# uicc.net
KiCad netlist of a schematic drawn in Altium Designer
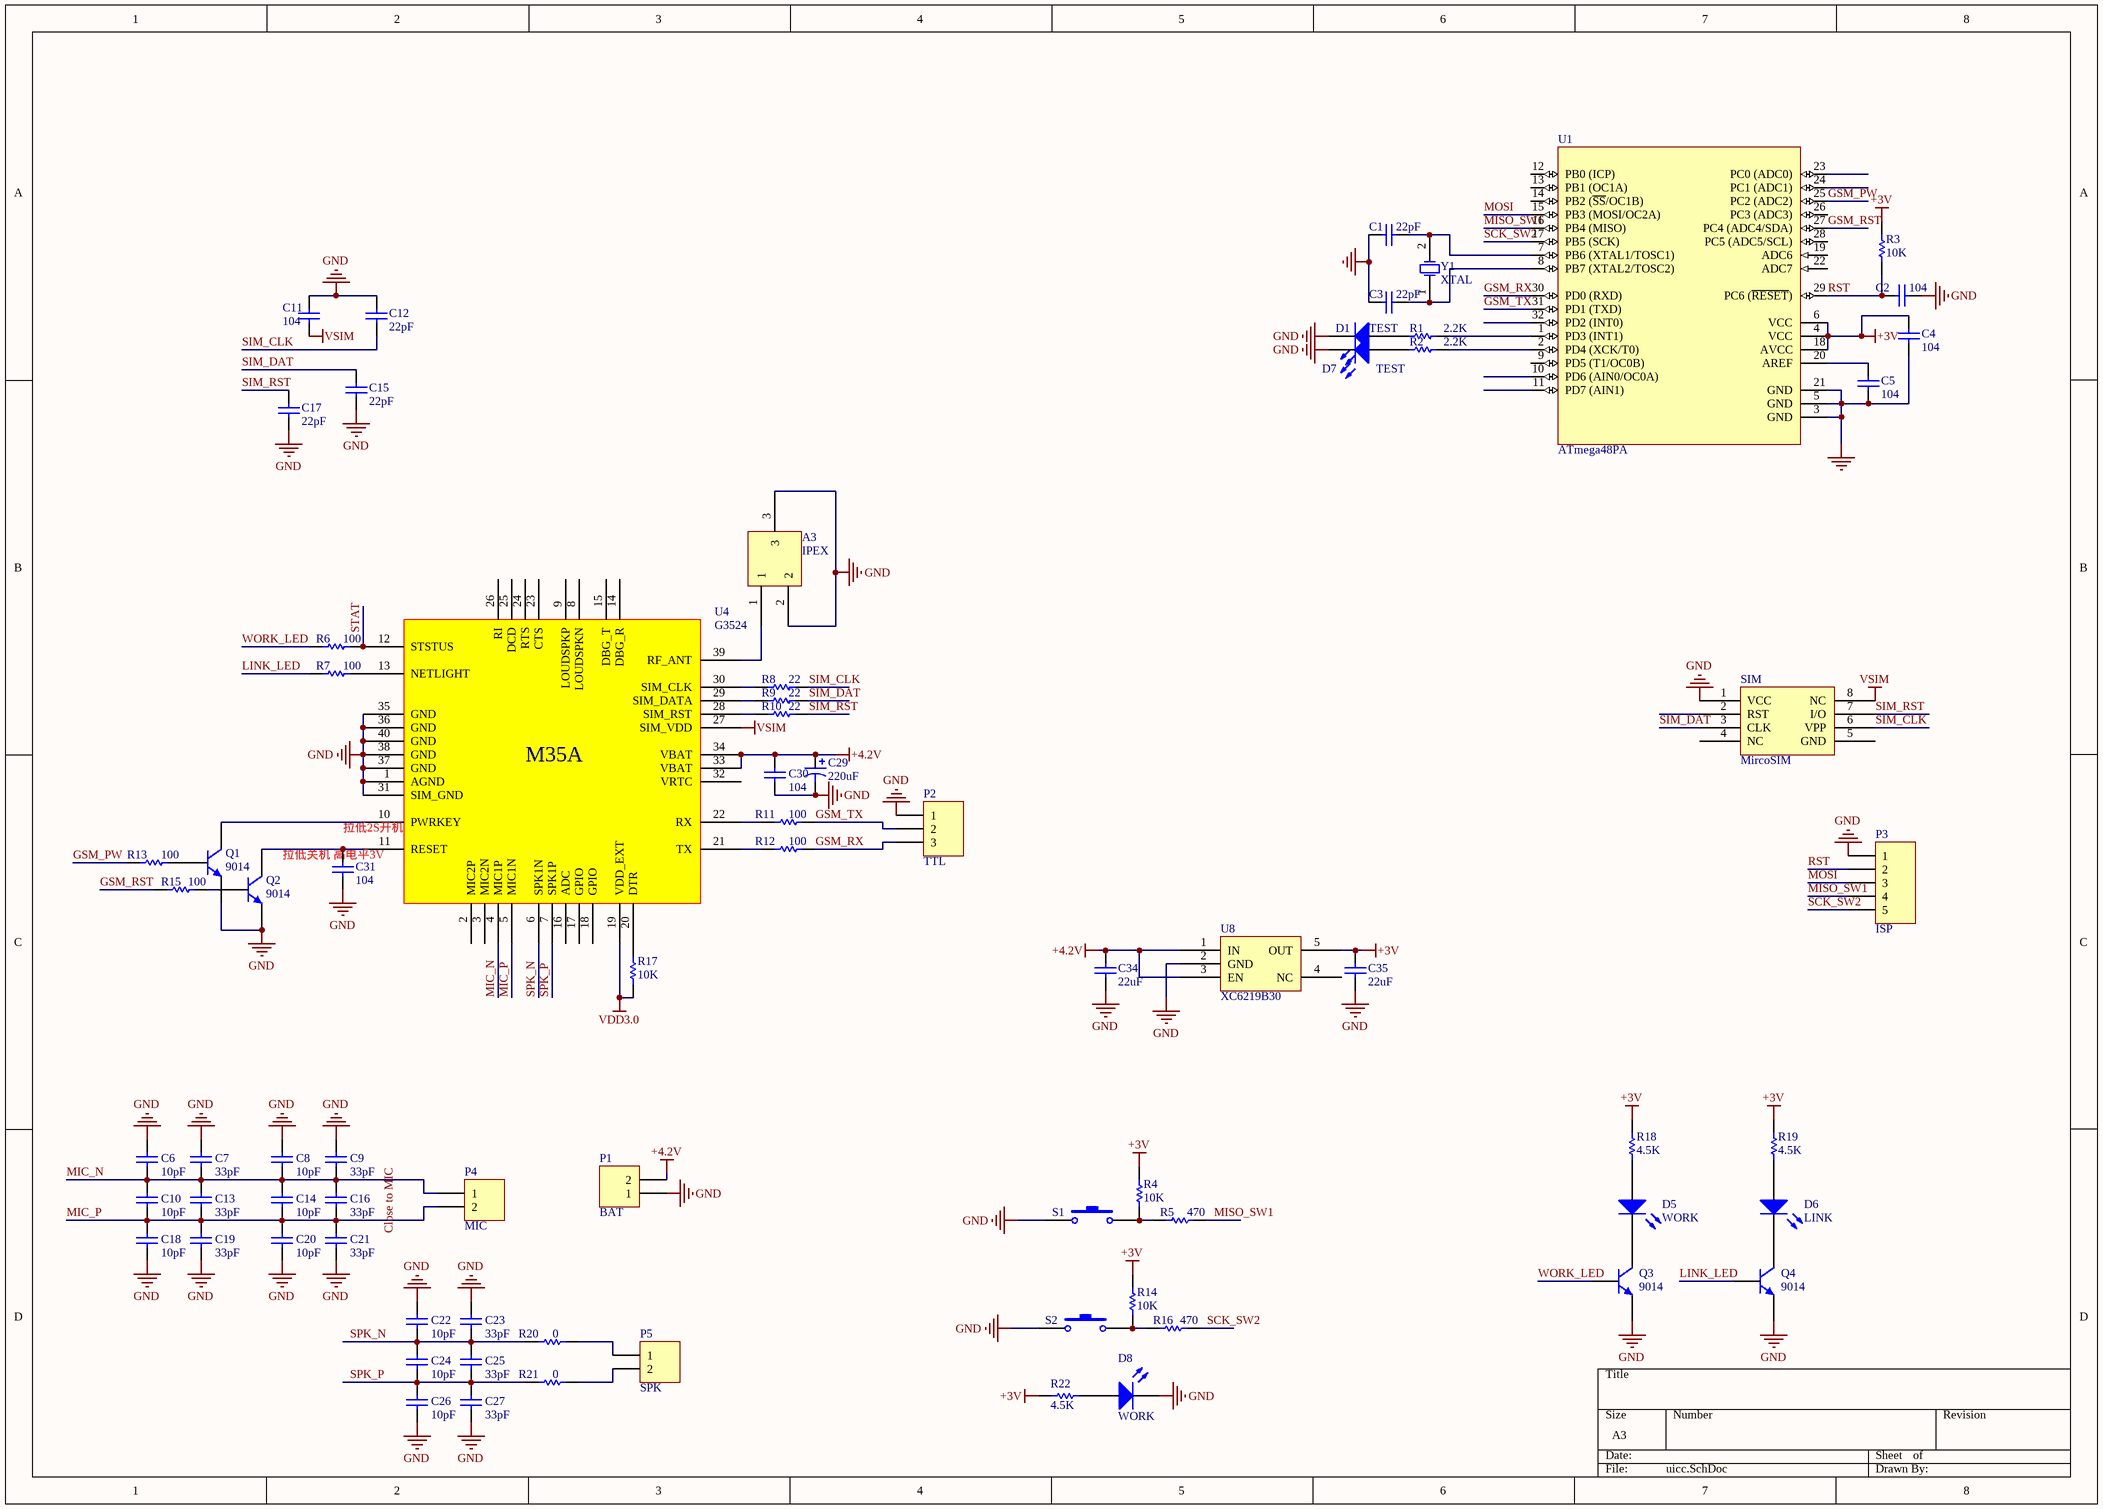
[diagram p0: uicc.SchDoc]

(export (version "E")
  (design (tool "Eeschema 10.0.6"))
  (components
    (comp (ref "A3") (value "IPEX") (footprint "IPEX") (libsource (lib "TANK") (part "IPEX")))
    (comp (ref "C1")
      (value "22pF")
      (footprint "0603C")
      (description "Capacitor")
      (fields (field (name "Comment") "Cap") (field (name "PUBLISHER") "Altium Limited"))
      (libsource (lib "*") (part "Cap"))
    )
    (comp (ref "C2")
      (value "104")
      (footprint "0603C")
      (description "Capacitor")
      (fields (field (name "Comment") "Cap") (field (name "PUBLISHER") "Altium Limited"))
      (libsource (lib "Miscellaneous Devices") (part "Cap"))
    )
    (comp (ref "C3")
      (value "22pF")
      (footprint "0603C")
      (description "Capacitor")
      (fields (field (name "Comment") "Cap") (field (name "PUBLISHER") "Altium Limited"))
      (libsource (lib "*") (part "Cap"))
    )
    (comp (ref "C4")
      (value "104")
      (footprint "0603C")
      (description "Capacitor")
      (fields (field (name "Comment") "Cap") (field (name "PUBLISHER") "Altium Limited"))
      (libsource (lib "Miscellaneous Devices") (part "Cap"))
    )
    (comp (ref "C5")
      (value "104")
      (footprint "0603C")
      (description "Capacitor")
      (fields (field (name "Comment") "Cap") (field (name "PUBLISHER") "Altium Limited"))
      (libsource (lib "*") (part "Cap"))
    )
    (comp (ref "C6")
      (value "10pF")
      (footprint "0603R")
      (description "Capacitor")
      (fields (field (name "Comment") "Cap") (field (name "PUBLISHER") "Altium Limited"))
      (libsource (lib "Miscellaneous Devices") (part "Cap"))
    )
    (comp (ref "C7")
      (value "33pF")
      (footprint "0603R")
      (description "Capacitor")
      (fields (field (name "Comment") "Cap") (field (name "PUBLISHER") "Altium Limited"))
      (libsource (lib "Miscellaneous Devices") (part "Cap"))
    )
    (comp (ref "C8")
      (value "10pF")
      (footprint "0603R")
      (description "Capacitor")
      (fields (field (name "Comment") "Cap") (field (name "PUBLISHER") "Altium Limited"))
      (libsource (lib "Miscellaneous Devices") (part "Cap"))
    )
    (comp (ref "C9")
      (value "33pF")
      (footprint "0603R")
      (description "Capacitor")
      (fields (field (name "Comment") "Cap") (field (name "PUBLISHER") "Altium Limited"))
      (libsource (lib "Miscellaneous Devices") (part "Cap"))
    )
    (comp (ref "C10")
      (value "10pF")
      (footprint "0603R")
      (description "Capacitor")
      (fields (field (name "Comment") "Cap") (field (name "PUBLISHER") "Altium Limited"))
      (libsource (lib "Miscellaneous Devices") (part "Cap"))
    )
    (comp (ref "C11")
      (value "104")
      (footprint "0603R")
      (description "Capacitor")
      (fields (field (name "Comment") "Cap") (field (name "PUBLISHER") "Altium Limited"))
      (libsource (lib "Miscellaneous Devices") (part "Cap"))
    )
    (comp (ref "C12")
      (value "22pF")
      (footprint "0603R")
      (description "Capacitor")
      (fields (field (name "Comment") "Cap") (field (name "PUBLISHER") "Altium Limited"))
      (libsource (lib "Miscellaneous Devices") (part "Cap"))
    )
    (comp (ref "C13")
      (value "33pF")
      (footprint "0603R")
      (description "Capacitor")
      (fields (field (name "Comment") "Cap") (field (name "PUBLISHER") "Altium Limited"))
      (libsource (lib "Miscellaneous Devices") (part "Cap"))
    )
    (comp (ref "C14")
      (value "10pF")
      (footprint "0603R")
      (description "Capacitor")
      (fields (field (name "Comment") "Cap") (field (name "PUBLISHER") "Altium Limited"))
      (libsource (lib "Miscellaneous Devices") (part "Cap"))
    )
    (comp (ref "C15")
      (value "22pF")
      (footprint "0603R")
      (description "Capacitor")
      (fields (field (name "Comment") "Cap") (field (name "PUBLISHER") "Altium Limited"))
      (libsource (lib "Miscellaneous Devices") (part "Cap"))
    )
    (comp (ref "C16")
      (value "33pF")
      (footprint "0603R")
      (description "Capacitor")
      (fields (field (name "Comment") "Cap") (field (name "PUBLISHER") "Altium Limited"))
      (libsource (lib "Miscellaneous Devices") (part "Cap"))
    )
    (comp (ref "C17")
      (value "22pF")
      (footprint "0603R")
      (description "Capacitor")
      (fields (field (name "Comment") "Cap") (field (name "PUBLISHER") "Altium Limited"))
      (libsource (lib "Miscellaneous Devices") (part "Cap"))
    )
    (comp (ref "C18")
      (value "10pF")
      (footprint "0603R")
      (description "Capacitor")
      (fields (field (name "Comment") "Cap") (field (name "PUBLISHER") "Altium Limited"))
      (libsource (lib "Miscellaneous Devices") (part "Cap"))
    )
    (comp (ref "C19")
      (value "33pF")
      (footprint "0603R")
      (description "Capacitor")
      (fields (field (name "Comment") "Cap") (field (name "PUBLISHER") "Altium Limited"))
      (libsource (lib "Miscellaneous Devices") (part "Cap"))
    )
    (comp (ref "C20")
      (value "10pF")
      (footprint "0603R")
      (description "Capacitor")
      (fields (field (name "Comment") "Cap") (field (name "PUBLISHER") "Altium Limited"))
      (libsource (lib "Miscellaneous Devices") (part "Cap"))
    )
    (comp (ref "C21")
      (value "33pF")
      (footprint "0603R")
      (description "Capacitor")
      (fields (field (name "Comment") "Cap") (field (name "PUBLISHER") "Altium Limited"))
      (libsource (lib "Miscellaneous Devices") (part "Cap"))
    )
    (comp (ref "C22")
      (value "10pF")
      (footprint "0603R")
      (description "Capacitor")
      (fields (field (name "Comment") "Cap") (field (name "PUBLISHER") "Altium Limited"))
      (libsource (lib "Miscellaneous Devices") (part "Cap"))
    )
    (comp (ref "C23")
      (value "33pF")
      (footprint "0603R")
      (description "Capacitor")
      (fields (field (name "Comment") "Cap") (field (name "PUBLISHER") "Altium Limited"))
      (libsource (lib "Miscellaneous Devices") (part "Cap"))
    )
    (comp (ref "C24")
      (value "10pF")
      (footprint "0603R")
      (description "Capacitor")
      (fields (field (name "Comment") "Cap") (field (name "PUBLISHER") "Altium Limited"))
      (libsource (lib "Miscellaneous Devices") (part "Cap"))
    )
    (comp (ref "C25")
      (value "33pF")
      (footprint "0603R")
      (description "Capacitor")
      (fields (field (name "Comment") "Cap") (field (name "PUBLISHER") "Altium Limited"))
      (libsource (lib "Miscellaneous Devices") (part "Cap"))
    )
    (comp (ref "C26")
      (value "10pF")
      (footprint "0603R")
      (description "Capacitor")
      (fields (field (name "Comment") "Cap") (field (name "PUBLISHER") "Altium Limited"))
      (libsource (lib "Miscellaneous Devices") (part "Cap"))
    )
    (comp (ref "C27")
      (value "33pF")
      (footprint "0603R")
      (description "Capacitor")
      (fields (field (name "Comment") "Cap") (field (name "PUBLISHER") "Altium Limited"))
      (libsource (lib "Miscellaneous Devices") (part "Cap"))
    )
    (comp (ref "C29")
      (value "220uF")
      (footprint "C3216")
      (description "Polarized Capacitor (Surface Mount)")
      (fields (field (name "Comment") "Cap Pol3") (field (name "PUBLISHER") "Altium Limited"))
      (libsource (lib "Miscellaneous Devices") (part "Cap Pol3"))
    )
    (comp (ref "C30")
      (value "104")
      (footprint "0603R")
      (description "Capacitor")
      (fields (field (name "Comment") "Cap") (field (name "PUBLISHER") "Altium Limited"))
      (libsource (lib "Miscellaneous Devices") (part "Cap"))
    )
    (comp (ref "C31")
      (value "104")
      (footprint "0603R")
      (description "Capacitor")
      (fields (field (name "Comment") "Cap") (field (name "PUBLISHER") "Altium Limited"))
      (libsource (lib "Miscellaneous Devices") (part "Cap"))
    )
    (comp (ref "C34")
      (value "22uF")
      (footprint "C1206")
      (description "Capacitor")
      (fields (field (name "Comment") "Cap") (field (name "PUBLISHER") "Altium Limited"))
      (libsource (lib "Miscellaneous Devices") (part "Cap"))
    )
    (comp (ref "C35")
      (value "22uF")
      (footprint "C1206")
      (description "Capacitor")
      (fields (field (name "Comment") "Cap") (field (name "PUBLISHER") "Altium Limited"))
      (libsource (lib "Miscellaneous Devices") (part "Cap"))
    )
    (comp (ref "D1")
      (value "TEST")
      (footprint "0603-LED")
      (description "Typical RED, GREEN, YELLOW, AMBER GaAs LED")
      (fields (field (name "PUBLISHER") "Altium Limited"))
      (libsource (lib "Miscellaneous Devices") (part "LED2"))
    )
    (comp (ref "D5")
      (value "WORK")
      (footprint "0603-LED")
      (description "Typical RED, GREEN, YELLOW, AMBER GaAs LED")
      (fields (field (name "PUBLISHER") "Altium Limited"))
      (libsource (lib "Miscellaneous Devices") (part "LED2"))
    )
    (comp (ref "D6")
      (value "LINK")
      (footprint "0603-LED")
      (description "Typical RED, GREEN, YELLOW, AMBER GaAs LED")
      (fields (field (name "PUBLISHER") "Altium Limited"))
      (libsource (lib "Miscellaneous Devices") (part "LED2"))
    )
    (comp (ref "D7")
      (value "TEST")
      (footprint "0603-LED")
      (description "Typical RED, GREEN, YELLOW, AMBER GaAs LED")
      (fields (field (name "PUBLISHER") "Altium Limited"))
      (libsource (lib "Miscellaneous Devices") (part "LED2"))
    )
    (comp (ref "D8")
      (value "WORK")
      (footprint "0603-LED")
      (description "Typical RED, GREEN, YELLOW, AMBER GaAs LED")
      (fields (field (name "PUBLISHER") "Altium Limited"))
      (libsource (lib "Miscellaneous Devices") (part "LED2"))
    )
    (comp (ref "P1")
      (value "BAT")
      (footprint "PH2.0-2P")
      (description "Header, 2-Pin")
      (fields (field (name "PUBLISHER") "Altium Limited"))
      (libsource (lib "") (part "Header 2_1"))
    )
    (comp (ref "P2")
      (value "TTL")
      (footprint "HDR1X3")
      (description "Header, 3-Pin")
      (fields (field (name "PUBLISHER") "Altium Limited"))
      (libsource (lib "Miscellaneous Connectors") (part "Header 3"))
    )
    (comp (ref "P3")
      (value "ISP")
      (footprint "HDR1X5")
      (description "Header, 5-Pin")
      (fields (field (name "PUBLISHER") "Altium Limited"))
      (libsource (lib "Miscellaneous Connectors") (part "Header 5"))
    )
    (comp (ref "P4")
      (value "MIC")
      (footprint "PH2.0-2P")
      (description "Header, 2-Pin")
      (fields (field (name "PUBLISHER") "Altium Limited"))
      (libsource (lib "Miscellaneous Connectors") (part "Header 2"))
    )
    (comp (ref "P5")
      (value "SPK")
      (footprint "PH2.0-2P")
      (description "Header, 2-Pin")
      (fields (field (name "PUBLISHER") "Altium Limited"))
      (libsource (lib "Miscellaneous Connectors") (part "Header 2"))
    )
    (comp (ref "Q1")
      (value "9014")
      (footprint "SOT-23-NPN")
      (description "NPN General Purpose Amplifier")
      (fields (field (name "Comment") "NPN") (field (name "PUBLISHER") "Altium Limited"))
      (libsource (lib "FSC Discrete BJT") (part "2N5551"))
    )
    (comp (ref "Q2")
      (value "9014")
      (footprint "SOT-23-NPN")
      (description "NPN General Purpose Amplifier")
      (fields (field (name "Comment") "NPN") (field (name "PUBLISHER") "Altium Limited"))
      (libsource (lib "FSC Discrete BJT") (part "2N5551"))
    )
    (comp (ref "Q3")
      (value "9014")
      (footprint "SOT-23-NPN")
      (description "NPN General Purpose Amplifier")
      (fields (field (name "Comment") "NPN") (field (name "PUBLISHER") "Altium Limited"))
      (libsource (lib "FSC Discrete BJT") (part "2N5551"))
    )
    (comp (ref "Q4")
      (value "9014")
      (footprint "SOT-23-NPN")
      (description "NPN General Purpose Amplifier")
      (fields (field (name "Comment") "NPN") (field (name "PUBLISHER") "Altium Limited"))
      (libsource (lib "FSC Discrete BJT") (part "2N5551"))
    )
    (comp (ref "R1")
      (value "2.2K")
      (footprint "0603R")
      (description "Resistor")
      (fields (field (name "Comment") "Res1") (field (name "PUBLISHER") "Altium Limited"))
      (libsource (lib "Miscellaneous Devices") (part "Res1"))
    )
    (comp (ref "R2")
      (value "2.2K")
      (footprint "0603R")
      (description "Resistor")
      (fields (field (name "Comment") "Res1") (field (name "PUBLISHER") "Altium Limited"))
      (libsource (lib "Miscellaneous Devices") (part "Res1"))
    )
    (comp (ref "R3")
      (value "10K")
      (footprint "0603R")
      (description "Resistor")
      (fields (field (name "Comment") "Res1") (field (name "PUBLISHER") "Altium Limited"))
      (libsource (lib "Miscellaneous Devices") (part "Res1"))
    )
    (comp (ref "R4")
      (value "10K")
      (footprint "0603R")
      (description "Resistor")
      (fields (field (name "Comment") "Res1") (field (name "PUBLISHER") "Altium Limited"))
      (libsource (lib "Miscellaneous Devices") (part "Res1"))
    )
    (comp (ref "R5")
      (value "470")
      (footprint "0603R")
      (description "Resistor")
      (fields (field (name "Comment") "Res1") (field (name "PUBLISHER") "Altium Limited"))
      (libsource (lib "Miscellaneous Devices") (part "Res1"))
    )
    (comp (ref "R6")
      (value "100")
      (footprint "0603R")
      (description "Resistor")
      (fields (field (name "Comment") "Res1") (field (name "PUBLISHER") "Altium Limited"))
      (libsource (lib "Miscellaneous Devices") (part "Res1"))
    )
    (comp (ref "R7")
      (value "100")
      (footprint "0603R")
      (description "Resistor")
      (fields (field (name "Comment") "Res1") (field (name "PUBLISHER") "Altium Limited"))
      (libsource (lib "Miscellaneous Devices") (part "Res1"))
    )
    (comp (ref "R8")
      (value "22")
      (footprint "0603R")
      (description "Resistor")
      (fields (field (name "Comment") "Res1") (field (name "PUBLISHER") "Altium Limited"))
      (libsource (lib "Miscellaneous Devices") (part "Res1"))
    )
    (comp (ref "R9")
      (value "22")
      (footprint "0603R")
      (description "Resistor")
      (fields (field (name "Comment") "Res1") (field (name "PUBLISHER") "Altium Limited"))
      (libsource (lib "Miscellaneous Devices") (part "Res1"))
    )
    (comp (ref "R10")
      (value "22")
      (footprint "0603R")
      (description "Resistor")
      (fields (field (name "Comment") "Res1") (field (name "PUBLISHER") "Altium Limited"))
      (libsource (lib "Miscellaneous Devices") (part "Res1"))
    )
    (comp (ref "R11")
      (value "100")
      (footprint "0603R")
      (description "Resistor")
      (fields (field (name "Comment") "Res1") (field (name "PUBLISHER") "Altium Limited"))
      (libsource (lib "Miscellaneous Devices") (part "Res1"))
    )
    (comp (ref "R12")
      (value "100")
      (footprint "0603R")
      (description "Resistor")
      (fields (field (name "Comment") "Res1") (field (name "PUBLISHER") "Altium Limited"))
      (libsource (lib "Miscellaneous Devices") (part "Res1"))
    )
    (comp (ref "R13")
      (value "100")
      (footprint "0603R")
      (description "Resistor")
      (fields (field (name "Comment") "Res1") (field (name "PUBLISHER") "Altium Limited"))
      (libsource (lib "Miscellaneous Devices") (part "Res1"))
    )
    (comp (ref "R14")
      (value "10K")
      (footprint "0603R")
      (description "Resistor")
      (fields (field (name "Comment") "Res1") (field (name "PUBLISHER") "Altium Limited"))
      (libsource (lib "Miscellaneous Devices") (part "Res1"))
    )
    (comp (ref "R15")
      (value "100")
      (footprint "0603R")
      (description "Resistor")
      (fields (field (name "Comment") "Res1") (field (name "PUBLISHER") "Altium Limited"))
      (libsource (lib "Miscellaneous Devices") (part "Res1"))
    )
    (comp (ref "R16")
      (value "470")
      (footprint "0603R")
      (description "Resistor")
      (fields (field (name "Comment") "Res1") (field (name "PUBLISHER") "Altium Limited"))
      (libsource (lib "Miscellaneous Devices") (part "Res1"))
    )
    (comp (ref "R17")
      (value "10K")
      (footprint "0603R")
      (description "Resistor")
      (fields (field (name "Comment") "Res1") (field (name "PUBLISHER") "Altium Limited"))
      (libsource (lib "Miscellaneous Devices") (part "Res1"))
    )
    (comp (ref "R18")
      (value "4.5K")
      (footprint "0603R")
      (description "Resistor")
      (fields (field (name "Comment") "Res1") (field (name "PUBLISHER") "Altium Limited"))
      (libsource (lib "Miscellaneous Devices") (part "Res1"))
    )
    (comp (ref "R19")
      (value "4.5K")
      (footprint "0603R")
      (description "Resistor")
      (fields (field (name "Comment") "Res1") (field (name "PUBLISHER") "Altium Limited"))
      (libsource (lib "Miscellaneous Devices") (part "Res1"))
    )
    (comp (ref "R20")
      (value "0")
      (footprint "0603R")
      (description "Resistor")
      (fields (field (name "Comment") "Res1") (field (name "PUBLISHER") "Altium Limited"))
      (libsource (lib "Miscellaneous Devices") (part "Res1"))
    )
    (comp (ref "R21")
      (value "0")
      (footprint "0603R")
      (description "Resistor")
      (fields (field (name "Comment") "Res1") (field (name "PUBLISHER") "Altium Limited"))
      (libsource (lib "Miscellaneous Devices") (part "Res1"))
    )
    (comp (ref "R22")
      (value "4.5K")
      (footprint "0603R")
      (description "Resistor")
      (fields (field (name "Comment") "Res1") (field (name "PUBLISHER") "Altium Limited"))
      (libsource (lib "Miscellaneous Devices") (part "Res1"))
    )
    (comp (ref "S1")
      (value "SW-PB")
      (footprint "SW1")
      (description "Switch")
      (fields (field (name "PUBLISHER") "Altium Limited"))
      (libsource (lib "Miscellaneous Devices") (part "SW-PB"))
    )
    (comp (ref "S2")
      (value "SW-PB")
      (footprint "SW1")
      (description "Switch")
      (fields (field (name "PUBLISHER") "Altium Limited"))
      (libsource (lib "Miscellaneous Devices") (part "SW-PB"))
    )
    (comp (ref "SIM") (value "MircoSIM") (footprint "VQFN8") (libsource (lib "TANK") (part "MircoSIM")))
    (comp (ref "U1")
      (value "ATmega48PA")
      (footprint "32A_N")
      (description "8-Bit AVR Microcontroller with 8K Bytes of In-System Programmable Flash Memory")
      (fields (field (name "PUBLISHER") "Altium Limited"))
      (libsource (lib "*") (part "ATmega8-16AC"))
    )
    (comp (ref "U4") (value "G3524") (footprint "G3524") (libsource (lib "TANK") (part "G3524")))
    (comp (ref "U8") (value "XC6219B30") (footprint "SOT23-5N") (libsource (lib "TANK") (part "LP5907")))
    (comp (ref "Y1")
      (value "XTAL")
      (footprint "49SD")
      (description "Crystal Oscillator")
      (fields (field (name "PUBLISHER") "Altium Limited"))
      (libsource (lib "*") (part "XTAL"))
    )
  )
  (nets
    (net (code "1") (name "+3V") (class "Default")
      (node (ref "C35") (pin "1") (pinfunction "1_1") (pintype "passive"))
      (node (ref "C4") (pin "2") (pinfunction "2_2") (pintype "passive"))
      (node (ref "R14") (pin "1") (pinfunction "1_1") (pintype "passive"))
      (node (ref "R18") (pin "1") (pinfunction "1_1") (pintype "passive"))
      (node (ref "R19") (pin "1") (pinfunction "1_1") (pintype "passive"))
      (node (ref "R22") (pin "1") (pinfunction "1_1") (pintype "passive"))
      (node (ref "R3") (pin "2") (pinfunction "2_2") (pintype "passive"))
      (node (ref "R4") (pin "1") (pinfunction "1_1") (pintype "passive"))
      (node (ref "U1") (pin "18") (pinfunction "AVCC_18") (pintype "power_in"))
      (node (ref "U1") (pin "4") (pinfunction "VCC_4") (pintype "power_in"))
      (node (ref "U1") (pin "6") (pinfunction "VCC_6") (pintype "power_in"))
      (node (ref "U8") (pin "5") (pinfunction "OUT_5") (pintype "passive"))
    )
    (net (code "2") (name "+4.2V") (class "Default")
      (node (ref "C29") (pin "1") (pinfunction "1_1") (pintype "passive"))
      (node (ref "C30") (pin "2") (pinfunction "2_2") (pintype "passive"))
      (node (ref "C34") (pin "1") (pinfunction "1_1") (pintype "passive"))
      (node (ref "P1") (pin "2") (pinfunction "2_2") (pintype "passive"))
      (node (ref "U4") (pin "33") (pinfunction "VBAT_33") (pintype "passive"))
      (node (ref "U4") (pin "34") (pinfunction "VBAT_34") (pintype "passive"))
      (node (ref "U8") (pin "1") (pinfunction "IN_1") (pintype "passive"))
      (node (ref "U8") (pin "3") (pinfunction "EN_3") (pintype "passive"))
    )
    (net (code "4") (name "/GSM_PW") (class "Default")
      (node (ref "R13") (pin "2") (pinfunction "2_2") (pintype "passive"))
      (node (ref "U1") (pin "25") (pinfunction "PC2_(ADC2)_25") (pintype "bidirectional"))
    )
    (net (code "5") (name "/GSM_RST") (class "Default")
      (node (ref "R15") (pin "2") (pinfunction "2_2") (pintype "passive"))
      (node (ref "U1") (pin "27") (pinfunction "PC4_(ADC4/SDA)_27") (pintype "bidirectional"))
    )
    (net (code "6") (name "/GSM_RX") (class "Default")
      (node (ref "P2") (pin "3") (pinfunction "3_3") (pintype "passive"))
      (node (ref "R12") (pin "2") (pinfunction "2_2") (pintype "passive"))
      (node (ref "U1") (pin "30") (pinfunction "PD0_(RXD)_30") (pintype "bidirectional"))
    )
    (net (code "7") (name "/GSM_TX") (class "Default")
      (node (ref "P2") (pin "2") (pinfunction "2_2") (pintype "passive"))
      (node (ref "R11") (pin "2") (pinfunction "2_2") (pintype "passive"))
      (node (ref "U1") (pin "31") (pinfunction "PD1_(TXD)_31") (pintype "bidirectional"))
    )
    (net (code "8") (name "/LINK_LED") (class "Default")
      (node (ref "Q4") (pin "2") (pinfunction "B_2") (pintype "passive"))
      (node (ref "R7") (pin "2") (pinfunction "2_2") (pintype "passive"))
    )
    (net (code "9") (name "/MIC_N") (class "Default")
      (node (ref "C10") (pin "2") (pinfunction "2_2") (pintype "passive"))
      (node (ref "C13") (pin "2") (pinfunction "2_2") (pintype "passive"))
      (node (ref "C14") (pin "2") (pinfunction "2_2") (pintype "passive"))
      (node (ref "C16") (pin "2") (pinfunction "2_2") (pintype "passive"))
      (node (ref "C6") (pin "1") (pinfunction "1_1") (pintype "passive"))
      (node (ref "C7") (pin "1") (pinfunction "1_1") (pintype "passive"))
      (node (ref "C8") (pin "1") (pinfunction "1_1") (pintype "passive"))
      (node (ref "C9") (pin "1") (pinfunction "1_1") (pintype "passive"))
      (node (ref "P4") (pin "1") (pinfunction "1_1") (pintype "passive"))
      (node (ref "U4") (pin "4") (pinfunction "MIC1P_4") (pintype "passive"))
    )
    (net (code "10") (name "/MIC_P") (class "Default")
      (node (ref "C10") (pin "1") (pinfunction "1_1") (pintype "passive"))
      (node (ref "C13") (pin "1") (pinfunction "1_1") (pintype "passive"))
      (node (ref "C14") (pin "1") (pinfunction "1_1") (pintype "passive"))
      (node (ref "C16") (pin "1") (pinfunction "1_1") (pintype "passive"))
      (node (ref "C18") (pin "2") (pinfunction "2_2") (pintype "passive"))
      (node (ref "C19") (pin "2") (pinfunction "2_2") (pintype "passive"))
      (node (ref "C20") (pin "2") (pinfunction "2_2") (pintype "passive"))
      (node (ref "C21") (pin "2") (pinfunction "2_2") (pintype "passive"))
      (node (ref "P4") (pin "2") (pinfunction "2_2") (pintype "passive"))
      (node (ref "U4") (pin "5") (pinfunction "MIC1N_5") (pintype "passive"))
    )
    (net (code "11") (name "/MISO_SW1") (class "Default")
      (node (ref "P3") (pin "4") (pinfunction "4_4") (pintype "passive"))
      (node (ref "R5") (pin "2") (pinfunction "2_2") (pintype "passive"))
      (node (ref "U1") (pin "16") (pinfunction "PB4_(MISO)_16") (pintype "bidirectional"))
    )
    (net (code "12") (name "/MOSI") (class "Default")
      (node (ref "P3") (pin "3") (pinfunction "3_3") (pintype "passive"))
      (node (ref "U1") (pin "15") (pinfunction "PB3_(MOSI/OC2A)_15") (pintype "bidirectional"))
    )
    (net (code "13") (name "/RST") (class "Default")
      (node (ref "C2") (pin "1") (pinfunction "1_1") (pintype "passive"))
      (node (ref "P3") (pin "2") (pinfunction "2_2") (pintype "passive"))
      (node (ref "R3") (pin "1") (pinfunction "1_1") (pintype "passive"))
      (node (ref "U1") (pin "29") (pinfunction "PC6_(~{RESET})_29") (pintype "bidirectional"))
    )
    (net (code "14") (name "/SCK_SW2") (class "Default")
      (node (ref "P3") (pin "5") (pinfunction "5_5") (pintype "passive"))
      (node (ref "R16") (pin "2") (pinfunction "2_2") (pintype "passive"))
      (node (ref "U1") (pin "17") (pinfunction "PB5_(SCK)_17") (pintype "bidirectional"))
    )
    (net (code "15") (name "/SIM_CLK") (class "Default")
      (node (ref "C12") (pin "2") (pinfunction "2_2") (pintype "passive"))
      (node (ref "R8") (pin "1") (pinfunction "1_1") (pintype "passive"))
      (node (ref "SIM") (pin "6") (pinfunction "VPP_6") (pintype "passive"))
    )
    (net (code "16") (name "/SIM_DAT") (class "Default")
      (node (ref "C15") (pin "1") (pinfunction "1_1") (pintype "passive"))
      (node (ref "R9") (pin "1") (pinfunction "1_1") (pintype "passive"))
      (node (ref "SIM") (pin "3") (pinfunction "CLK_3") (pintype "passive"))
    )
    (net (code "17") (name "/SIM_RST") (class "Default")
      (node (ref "C17") (pin "1") (pinfunction "1_1") (pintype "passive"))
      (node (ref "R10") (pin "1") (pinfunction "1_1") (pintype "passive"))
      (node (ref "SIM") (pin "7") (pinfunction "I/O_7") (pintype "passive"))
    )
    (net (code "18") (name "/SPK_N") (class "Default")
      (node (ref "C22") (pin "1") (pinfunction "1_1") (pintype "passive"))
      (node (ref "C23") (pin "1") (pinfunction "1_1") (pintype "passive"))
      (node (ref "C24") (pin "2") (pinfunction "2_2") (pintype "passive"))
      (node (ref "C25") (pin "2") (pinfunction "2_2") (pintype "passive"))
      (node (ref "R20") (pin "1") (pinfunction "1_1") (pintype "passive"))
      (node (ref "U4") (pin "6") (pinfunction "SPK1N_6") (pintype "passive"))
    )
    (net (code "19") (name "/SPK_P") (class "Default")
      (node (ref "C24") (pin "1") (pinfunction "1_1") (pintype "passive"))
      (node (ref "C25") (pin "1") (pinfunction "1_1") (pintype "passive"))
      (node (ref "C26") (pin "2") (pinfunction "2_2") (pintype "passive"))
      (node (ref "C27") (pin "2") (pinfunction "2_2") (pintype "passive"))
      (node (ref "R21") (pin "1") (pinfunction "1_1") (pintype "passive"))
      (node (ref "U4") (pin "7") (pinfunction "SPK1P_7") (pintype "passive"))
    )
    (net (code "20") (name "/STAT") (class "Default")
      (node (ref "R6") (pin "1") (pinfunction "1_1") (pintype "passive"))
      (node (ref "U4") (pin "12") (pinfunction "STSTUS_12") (pintype "passive"))
    )
    (net (code "21") (name "/WORK_LED") (class "Default")
      (node (ref "Q3") (pin "2") (pinfunction "B_2") (pintype "passive"))
      (node (ref "R6") (pin "2") (pinfunction "2_2") (pintype "passive"))
    )
    (net (code "22") (name "GND") (class "Default")
      (node (ref "A3") (pin "2") (pinfunction "2_2") (pintype "passive"))
      (node (ref "A3") (pin "3") (pinfunction "3_3") (pintype "passive"))
      (node (ref "C1") (pin "2") (pinfunction "2_2") (pintype "passive"))
      (node (ref "C11") (pin "1") (pinfunction "1_1") (pintype "passive"))
      (node (ref "C12") (pin "1") (pinfunction "1_1") (pintype "passive"))
      (node (ref "C15") (pin "2") (pinfunction "2_2") (pintype "passive"))
      (node (ref "C17") (pin "2") (pinfunction "2_2") (pintype "passive"))
      (node (ref "C18") (pin "1") (pinfunction "1_1") (pintype "passive"))
      (node (ref "C19") (pin "1") (pinfunction "1_1") (pintype "passive"))
      (node (ref "C2") (pin "2") (pinfunction "2_2") (pintype "passive"))
      (node (ref "C20") (pin "1") (pinfunction "1_1") (pintype "passive"))
      (node (ref "C21") (pin "1") (pinfunction "1_1") (pintype "passive"))
      (node (ref "C22") (pin "2") (pinfunction "2_2") (pintype "passive"))
      (node (ref "C23") (pin "2") (pinfunction "2_2") (pintype "passive"))
      (node (ref "C26") (pin "1") (pinfunction "1_1") (pintype "passive"))
      (node (ref "C27") (pin "1") (pinfunction "1_1") (pintype "passive"))
      (node (ref "C29") (pin "2") (pinfunction "2_2") (pintype "passive"))
      (node (ref "C3") (pin "2") (pinfunction "2_2") (pintype "passive"))
      (node (ref "C30") (pin "1") (pinfunction "1_1") (pintype "passive"))
      (node (ref "C31") (pin "2") (pinfunction "2_2") (pintype "passive"))
      (node (ref "C34") (pin "2") (pinfunction "2_2") (pintype "passive"))
      (node (ref "C35") (pin "2") (pinfunction "2_2") (pintype "passive"))
      (node (ref "C4") (pin "1") (pinfunction "1_1") (pintype "passive"))
      (node (ref "C5") (pin "2") (pinfunction "2_2") (pintype "passive"))
      (node (ref "C6") (pin "2") (pinfunction "2_2") (pintype "passive"))
      (node (ref "C7") (pin "2") (pinfunction "2_2") (pintype "passive"))
      (node (ref "C8") (pin "2") (pinfunction "2_2") (pintype "passive"))
      (node (ref "C9") (pin "2") (pinfunction "2_2") (pintype "passive"))
      (node (ref "D1") (pin "2") (pinfunction "K_2") (pintype "passive"))
      (node (ref "D7") (pin "2") (pinfunction "K_2") (pintype "passive"))
      (node (ref "D8") (pin "2") (pinfunction "K_2") (pintype "passive"))
      (node (ref "P1") (pin "1") (pinfunction "1_1") (pintype "passive"))
      (node (ref "P2") (pin "1") (pinfunction "1_1") (pintype "passive"))
      (node (ref "P3") (pin "1") (pinfunction "1_1") (pintype "passive"))
      (node (ref "Q1") (pin "1") (pinfunction "E_1") (pintype "passive"))
      (node (ref "Q2") (pin "1") (pinfunction "E_1") (pintype "passive"))
      (node (ref "Q3") (pin "1") (pinfunction "E_1") (pintype "passive"))
      (node (ref "Q4") (pin "1") (pinfunction "E_1") (pintype "passive"))
      (node (ref "S1") (pin "1") (pinfunction "1_1") (pintype "passive"))
      (node (ref "S2") (pin "1") (pinfunction "1_1") (pintype "passive"))
      (node (ref "SIM") (pin "1") (pinfunction "VCC_1") (pintype "passive"))
      (node (ref "U1") (pin "21") (pinfunction "GND_21") (pintype "power_in"))
      (node (ref "U1") (pin "3") (pinfunction "GND_3") (pintype "power_in"))
      (node (ref "U1") (pin "5") (pinfunction "GND_5") (pintype "power_in"))
      (node (ref "U4") (pin "1") (pinfunction "AGND_1") (pintype "passive"))
      (node (ref "U4") (pin "31") (pinfunction "SIM_GND_31") (pintype "passive"))
      (node (ref "U4") (pin "35") (pinfunction "GND_35") (pintype "passive"))
      (node (ref "U4") (pin "36") (pinfunction "GND_36") (pintype "passive"))
      (node (ref "U4") (pin "37") (pinfunction "GND_37") (pintype "passive"))
      (node (ref "U4") (pin "38") (pinfunction "GND_38") (pintype "passive"))
      (node (ref "U4") (pin "40") (pinfunction "GND_40") (pintype "passive"))
      (node (ref "U8") (pin "2") (pinfunction "GND_2") (pintype "passive"))
    )
    (net (code "23") (name "Net-(D1-A)") (class "Default")
      (node (ref "D1") (pin "1") (pinfunction "A_1") (pintype "passive"))
      (node (ref "R1") (pin "2") (pinfunction "2_2") (pintype "passive"))
    )
    (net (code "24") (name "Net-(D5-A)") (class "Default")
      (node (ref "D5") (pin "1") (pinfunction "A_1") (pintype "passive"))
      (node (ref "R18") (pin "2") (pinfunction "2_2") (pintype "passive"))
    )
    (net (code "25") (name "Net-(D5-K)") (class "Default")
      (node (ref "D5") (pin "2") (pinfunction "K_2") (pintype "passive"))
      (node (ref "Q3") (pin "3") (pinfunction "C_3") (pintype "passive"))
    )
    (net (code "26") (name "Net-(D6-A)") (class "Default")
      (node (ref "D6") (pin "1") (pinfunction "A_1") (pintype "passive"))
      (node (ref "R19") (pin "2") (pinfunction "2_2") (pintype "passive"))
    )
    (net (code "27") (name "Net-(D6-K)") (class "Default")
      (node (ref "D6") (pin "2") (pinfunction "K_2") (pintype "passive"))
      (node (ref "Q4") (pin "3") (pinfunction "C_3") (pintype "passive"))
    )
    (net (code "28") (name "Net-(D7-A)") (class "Default")
      (node (ref "D7") (pin "1") (pinfunction "A_1") (pintype "passive"))
      (node (ref "R2") (pin "2") (pinfunction "2_2") (pintype "passive"))
    )
    (net (code "29") (name "Net-(D8-A)") (class "Default")
      (node (ref "D8") (pin "1") (pinfunction "A_1") (pintype "passive"))
      (node (ref "R22") (pin "2") (pinfunction "2_2") (pintype "passive"))
    )
    (net (code "30") (name "Net-(P5-Pad1)") (class "Default")
      (node (ref "P5") (pin "1") (pinfunction "1_1") (pintype "passive"))
      (node (ref "R20") (pin "2") (pinfunction "2_2") (pintype "passive"))
    )
    (net (code "31") (name "Net-(P5-Pad2)") (class "Default")
      (node (ref "P5") (pin "2") (pinfunction "2_2") (pintype "passive"))
      (node (ref "R21") (pin "2") (pinfunction "2_2") (pintype "passive"))
    )
    (net (code "32") (name "Net-(Q1-B)") (class "Default")
      (node (ref "Q1") (pin "2") (pinfunction "B_2") (pintype "passive"))
      (node (ref "R13") (pin "1") (pinfunction "1_1") (pintype "passive"))
    )
    (net (code "33") (name "Net-(Q1-C)") (class "Default")
      (node (ref "Q1") (pin "3") (pinfunction "C_3") (pintype "passive"))
      (node (ref "U4") (pin "10") (pinfunction "PWRKEY_10") (pintype "passive"))
    )
    (net (code "34") (name "Net-(Q2-B)") (class "Default")
      (node (ref "Q2") (pin "2") (pinfunction "B_2") (pintype "passive"))
      (node (ref "R15") (pin "1") (pinfunction "1_1") (pintype "passive"))
    )
    (net (code "35") (name "Net-(Q2-C)") (class "Default")
      (node (ref "C31") (pin "1") (pinfunction "1_1") (pintype "passive"))
      (node (ref "Q2") (pin "3") (pinfunction "C_3") (pintype "passive"))
      (node (ref "U4") (pin "11") (pinfunction "RESET_11") (pintype "passive"))
    )
    (net (code "36") (name "Net-(R4-Pad2)") (class "Default")
      (node (ref "R4") (pin "2") (pinfunction "2_2") (pintype "passive"))
      (node (ref "R5") (pin "1") (pinfunction "1_1") (pintype "passive"))
      (node (ref "S1") (pin "2") (pinfunction "2_2") (pintype "passive"))
    )
    (net (code "37") (name "Net-(R14-Pad2)") (class "Default")
      (node (ref "R14") (pin "2") (pinfunction "2_2") (pintype "passive"))
      (node (ref "R16") (pin "1") (pinfunction "1_1") (pintype "passive"))
      (node (ref "S2") (pin "2") (pinfunction "2_2") (pintype "passive"))
    )
    (net (code "38") (name "Net-(U1-AREF)") (class "Default")
      (node (ref "C5") (pin "1") (pinfunction "1_1") (pintype "passive"))
      (node (ref "U1") (pin "20") (pinfunction "AREF_20") (pintype "passive"))
    )
    (net (code "39") (name "Net-(U1-PB6_(XTAL1{slash}TOSC1))") (class "Default")
      (node (ref "C1") (pin "1") (pinfunction "1_1") (pintype "passive"))
      (node (ref "U1") (pin "7") (pinfunction "PB6_(XTAL1/TOSC1)_7") (pintype "bidirectional"))
      (node (ref "Y1") (pin "2") (pinfunction "OSC2_2") (pintype "passive"))
    )
    (net (code "40") (name "Net-(U1-PB7_(XTAL2{slash}TOSC2))") (class "Default")
      (node (ref "C3") (pin "1") (pinfunction "1_1") (pintype "passive"))
      (node (ref "U1") (pin "8") (pinfunction "PB7_(XTAL2/TOSC2)_8") (pintype "bidirectional"))
      (node (ref "Y1") (pin "1") (pinfunction "OSC1_1") (pintype "passive"))
    )
    (net (code "41") (name "Net-(U1-PD3_(INT1))") (class "Default")
      (node (ref "R1") (pin "1") (pinfunction "1_1") (pintype "passive"))
      (node (ref "U1") (pin "1") (pinfunction "PD3_(INT1)_1") (pintype "bidirectional"))
    )
    (net (code "42") (name "Net-(U1-PD4_(XCK{slash}T0))") (class "Default")
      (node (ref "R2") (pin "1") (pinfunction "1_1") (pintype "passive"))
      (node (ref "U1") (pin "2") (pinfunction "PD4_(XCK/T0)_2") (pintype "bidirectional"))
    )
    (net (code "43") (name "Net-(U4-DTR)") (class "Default")
      (node (ref "R17") (pin "1") (pinfunction "1_1") (pintype "passive"))
      (node (ref "U4") (pin "20") (pinfunction "DTR_20") (pintype "passive"))
    )
    (net (code "44") (name "Net-(U4-NETLIGHT)") (class "Default")
      (node (ref "R7") (pin "1") (pinfunction "1_1") (pintype "passive"))
      (node (ref "U4") (pin "13") (pinfunction "NETLIGHT_13") (pintype "passive"))
    )
    (net (code "45") (name "Net-(U4-RF_ANT)") (class "Default")
      (node (ref "A3") (pin "1") (pinfunction "1_1") (pintype "passive"))
      (node (ref "U4") (pin "39") (pinfunction "RF_ANT_39") (pintype "passive"))
    )
    (net (code "46") (name "Net-(U4-RX)") (class "Default")
      (node (ref "R11") (pin "1") (pinfunction "1_1") (pintype "passive"))
      (node (ref "U4") (pin "22") (pinfunction "RX_22") (pintype "passive"))
    )
    (net (code "47") (name "Net-(U4-SIM_CLK)") (class "Default")
      (node (ref "R8") (pin "2") (pinfunction "2_2") (pintype "passive"))
      (node (ref "U4") (pin "30") (pinfunction "SIM_CLK_30") (pintype "passive"))
    )
    (net (code "48") (name "Net-(U4-SIM_DATA)") (class "Default")
      (node (ref "R9") (pin "2") (pinfunction "2_2") (pintype "passive"))
      (node (ref "U4") (pin "29") (pinfunction "SIM_DATA_29") (pintype "passive"))
    )
    (net (code "49") (name "Net-(U4-SIM_RST)") (class "Default")
      (node (ref "R10") (pin "2") (pinfunction "2_2") (pintype "passive"))
      (node (ref "U4") (pin "28") (pinfunction "SIM_RST_28") (pintype "passive"))
    )
    (net (code "50") (name "Net-(U4-TX)") (class "Default")
      (node (ref "R12") (pin "1") (pinfunction "1_1") (pintype "passive"))
      (node (ref "U4") (pin "21") (pinfunction "TX_21") (pintype "passive"))
    )
    (net (code "51") (name "VDD3.0") (class "Default")
      (node (ref "R17") (pin "2") (pinfunction "2_2") (pintype "passive"))
      (node (ref "U4") (pin "19") (pinfunction "VDD_EXT_19") (pintype "passive"))
    )
    (net (code "52") (name "VSIM") (class "Default")
      (node (ref "C11") (pin "2") (pinfunction "2_2") (pintype "passive"))
      (node (ref "SIM") (pin "8") (pinfunction "NC_8") (pintype "passive"))
      (node (ref "U4") (pin "27") (pinfunction "SIM_VDD_27") (pintype "passive"))
    )
    (net (code "53") (name "unconnected-(SIM-GND-Pad5)") (class "Default")
      (node (ref "SIM") (pin "5") (pinfunction "GND_5") (pintype "passive"))
    )
    (net (code "54") (name "unconnected-(SIM-NC-Pad4)") (class "Default")
      (node (ref "SIM") (pin "4") (pinfunction "NC_4") (pintype "passive"))
    )
    (net (code "55") (name "unconnected-(SIM-RST-Pad2)") (class "Default")
      (node (ref "SIM") (pin "2") (pinfunction "RST_2") (pintype "passive"))
    )
    (net (code "56") (name "unconnected-(U1-ADC6-Pad19)") (class "Default")
      (node (ref "U1") (pin "19") (pinfunction "ADC6_19") (pintype "input"))
    )
    (net (code "57") (name "unconnected-(U1-ADC7-Pad22)") (class "Default")
      (node (ref "U1") (pin "22") (pinfunction "ADC7_22") (pintype "input"))
    )
    (net (code "58") (name "unconnected-(U1-PB0_(ICP)-Pad12)") (class "Default")
      (node (ref "U1") (pin "12") (pinfunction "PB0_(ICP)_12") (pintype "bidirectional"))
    )
    (net (code "59") (name "unconnected-(U1-PB1_(OC1A)-Pad13)") (class "Default")
      (node (ref "U1") (pin "13") (pinfunction "PB1_(OC1A)_13") (pintype "bidirectional"))
    )
    (net (code "60") (name "unconnected-(U1-PB2_(~{SS}{slash}OC1B)-Pad14)") (class "Default")
      (node (ref "U1") (pin "14") (pinfunction "PB2_(~{SS}/OC1B)_14") (pintype "bidirectional"))
    )
    (net (code "61") (name "unconnected-(U1-PC0_(ADC0)-Pad23)") (class "Default")
      (node (ref "U1") (pin "23") (pinfunction "PC0_(ADC0)_23") (pintype "bidirectional"))
    )
    (net (code "62") (name "unconnected-(U1-PC1_(ADC1)-Pad24)") (class "Default")
      (node (ref "U1") (pin "24") (pinfunction "PC1_(ADC1)_24") (pintype "bidirectional"))
    )
    (net (code "63") (name "unconnected-(U1-PC3_(ADC3)-Pad26)") (class "Default")
      (node (ref "U1") (pin "26") (pinfunction "PC3_(ADC3)_26") (pintype "bidirectional"))
    )
    (net (code "64") (name "unconnected-(U1-PC5_(ADC5{slash}SCL)-Pad28)") (class "Default")
      (node (ref "U1") (pin "28") (pinfunction "PC5_(ADC5/SCL)_28") (pintype "bidirectional"))
    )
    (net (code "65") (name "unconnected-(U1-PD2_(INT0)-Pad32)") (class "Default")
      (node (ref "U1") (pin "32") (pinfunction "PD2_(INT0)_32") (pintype "bidirectional"))
    )
    (net (code "66") (name "unconnected-(U1-PD5_(T1{slash}OC0B)-Pad9)") (class "Default")
      (node (ref "U1") (pin "9") (pinfunction "PD5_(T1/OC0B)_9") (pintype "bidirectional"))
    )
    (net (code "67") (name "unconnected-(U1-PD6_(AIN0{slash}OC0A)-Pad10)") (class "Default")
      (node (ref "U1") (pin "10") (pinfunction "PD6_(AIN0/OC0A)_10") (pintype "bidirectional"))
    )
    (net (code "68") (name "unconnected-(U1-PD7_(AIN1)-Pad11)") (class "Default")
      (node (ref "U1") (pin "11") (pinfunction "PD7_(AIN1)_11") (pintype "bidirectional"))
    )
    (net (code "69") (name "unconnected-(U4-ADC-Pad16)") (class "Default")
      (node (ref "U4") (pin "16") (pinfunction "ADC_16") (pintype "passive"))
    )
    (net (code "70") (name "unconnected-(U4-CTS-Pad23)") (class "Default")
      (node (ref "U4") (pin "23") (pinfunction "CTS_23") (pintype "passive"))
    )
    (net (code "71") (name "unconnected-(U4-DBG_R-Pad14)") (class "Default")
      (node (ref "U4") (pin "14") (pinfunction "DBG_R_14") (pintype "passive"))
    )
    (net (code "72") (name "unconnected-(U4-DBG_T-Pad15)") (class "Default")
      (node (ref "U4") (pin "15") (pinfunction "DBG_T_15") (pintype "passive"))
    )
    (net (code "73") (name "unconnected-(U4-DCD-Pad25)") (class "Default")
      (node (ref "U4") (pin "25") (pinfunction "DCD_25") (pintype "passive"))
    )
    (net (code "74") (name "unconnected-(U4-GPIO-Pad17)") (class "Default")
      (node (ref "U4") (pin "17") (pinfunction "GPIO_17") (pintype "passive"))
    )
    (net (code "75") (name "unconnected-(U4-GPIO-Pad18)") (class "Default")
      (node (ref "U4") (pin "18") (pinfunction "GPIO_18") (pintype "passive"))
    )
    (net (code "76") (name "unconnected-(U4-LOUDSPKN-Pad8)") (class "Default")
      (node (ref "U4") (pin "8") (pinfunction "LOUDSPKN_8") (pintype "passive"))
    )
    (net (code "77") (name "unconnected-(U4-LOUDSPKP-Pad9)") (class "Default")
      (node (ref "U4") (pin "9") (pinfunction "LOUDSPKP_9") (pintype "passive"))
    )
    (net (code "78") (name "unconnected-(U4-MIC2N-Pad3)") (class "Default")
      (node (ref "U4") (pin "3") (pinfunction "MIC2N_3") (pintype "passive"))
    )
    (net (code "79") (name "unconnected-(U4-MIC2P-Pad2)") (class "Default")
      (node (ref "U4") (pin "2") (pinfunction "MIC2P_2") (pintype "passive"))
    )
    (net (code "80") (name "unconnected-(U4-RI-Pad26)") (class "Default")
      (node (ref "U4") (pin "26") (pinfunction "RI_26") (pintype "passive"))
    )
    (net (code "81") (name "unconnected-(U4-RTS-Pad24)") (class "Default")
      (node (ref "U4") (pin "24") (pinfunction "RTS_24") (pintype "passive"))
    )
    (net (code "82") (name "unconnected-(U4-VRTC-Pad32)") (class "Default")
      (node (ref "U4") (pin "32") (pinfunction "VRTC_32") (pintype "passive"))
    )
    (net (code "83") (name "unconnected-(U8-NC-Pad4)") (class "Default")
      (node (ref "U8") (pin "4") (pinfunction "NC_4") (pintype "passive"))
    )
  )
)
